# CON_REVC.net
KiCad netlist of a schematic drawn in EAGLE
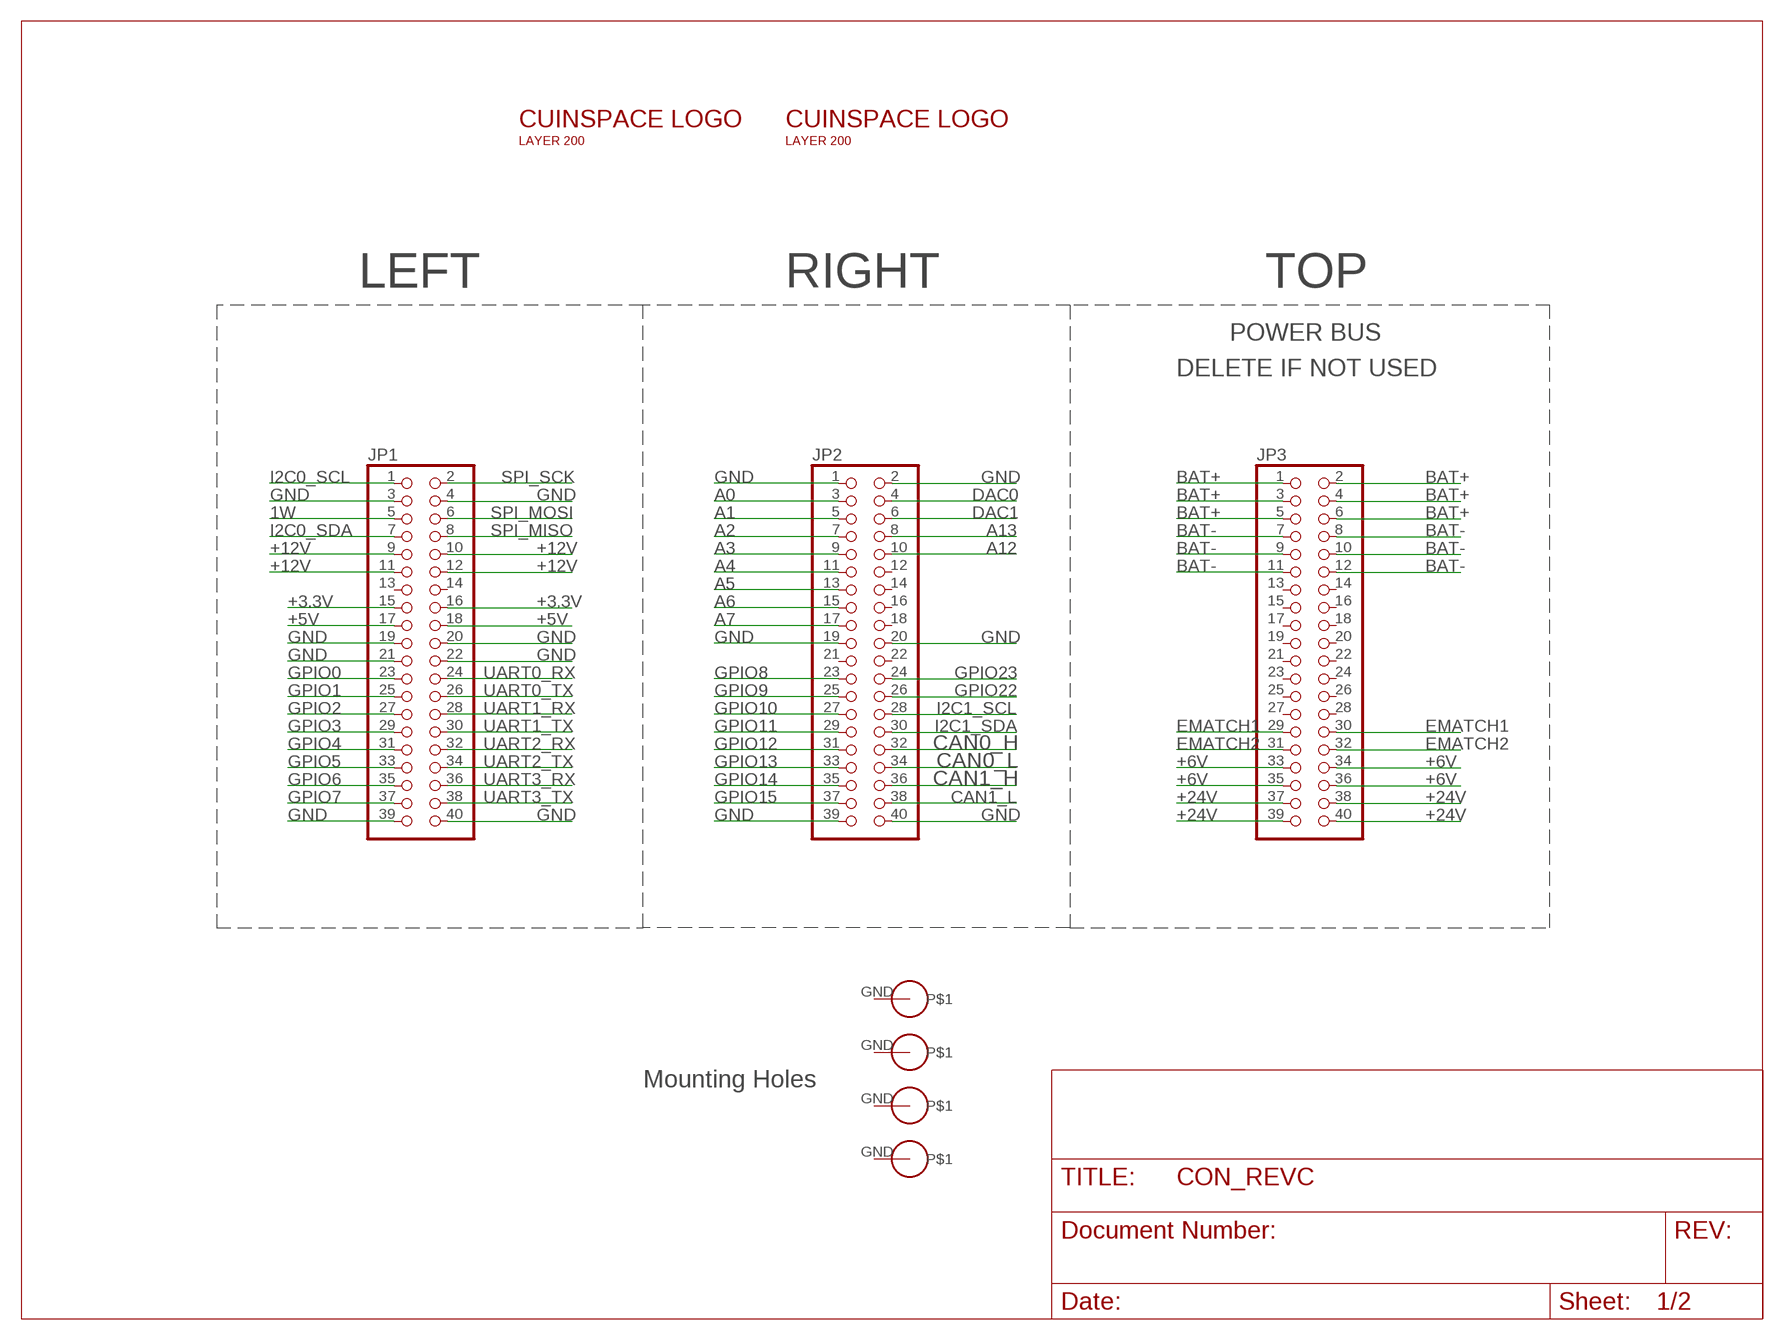
[diagram p0: schematic, sheet 1]
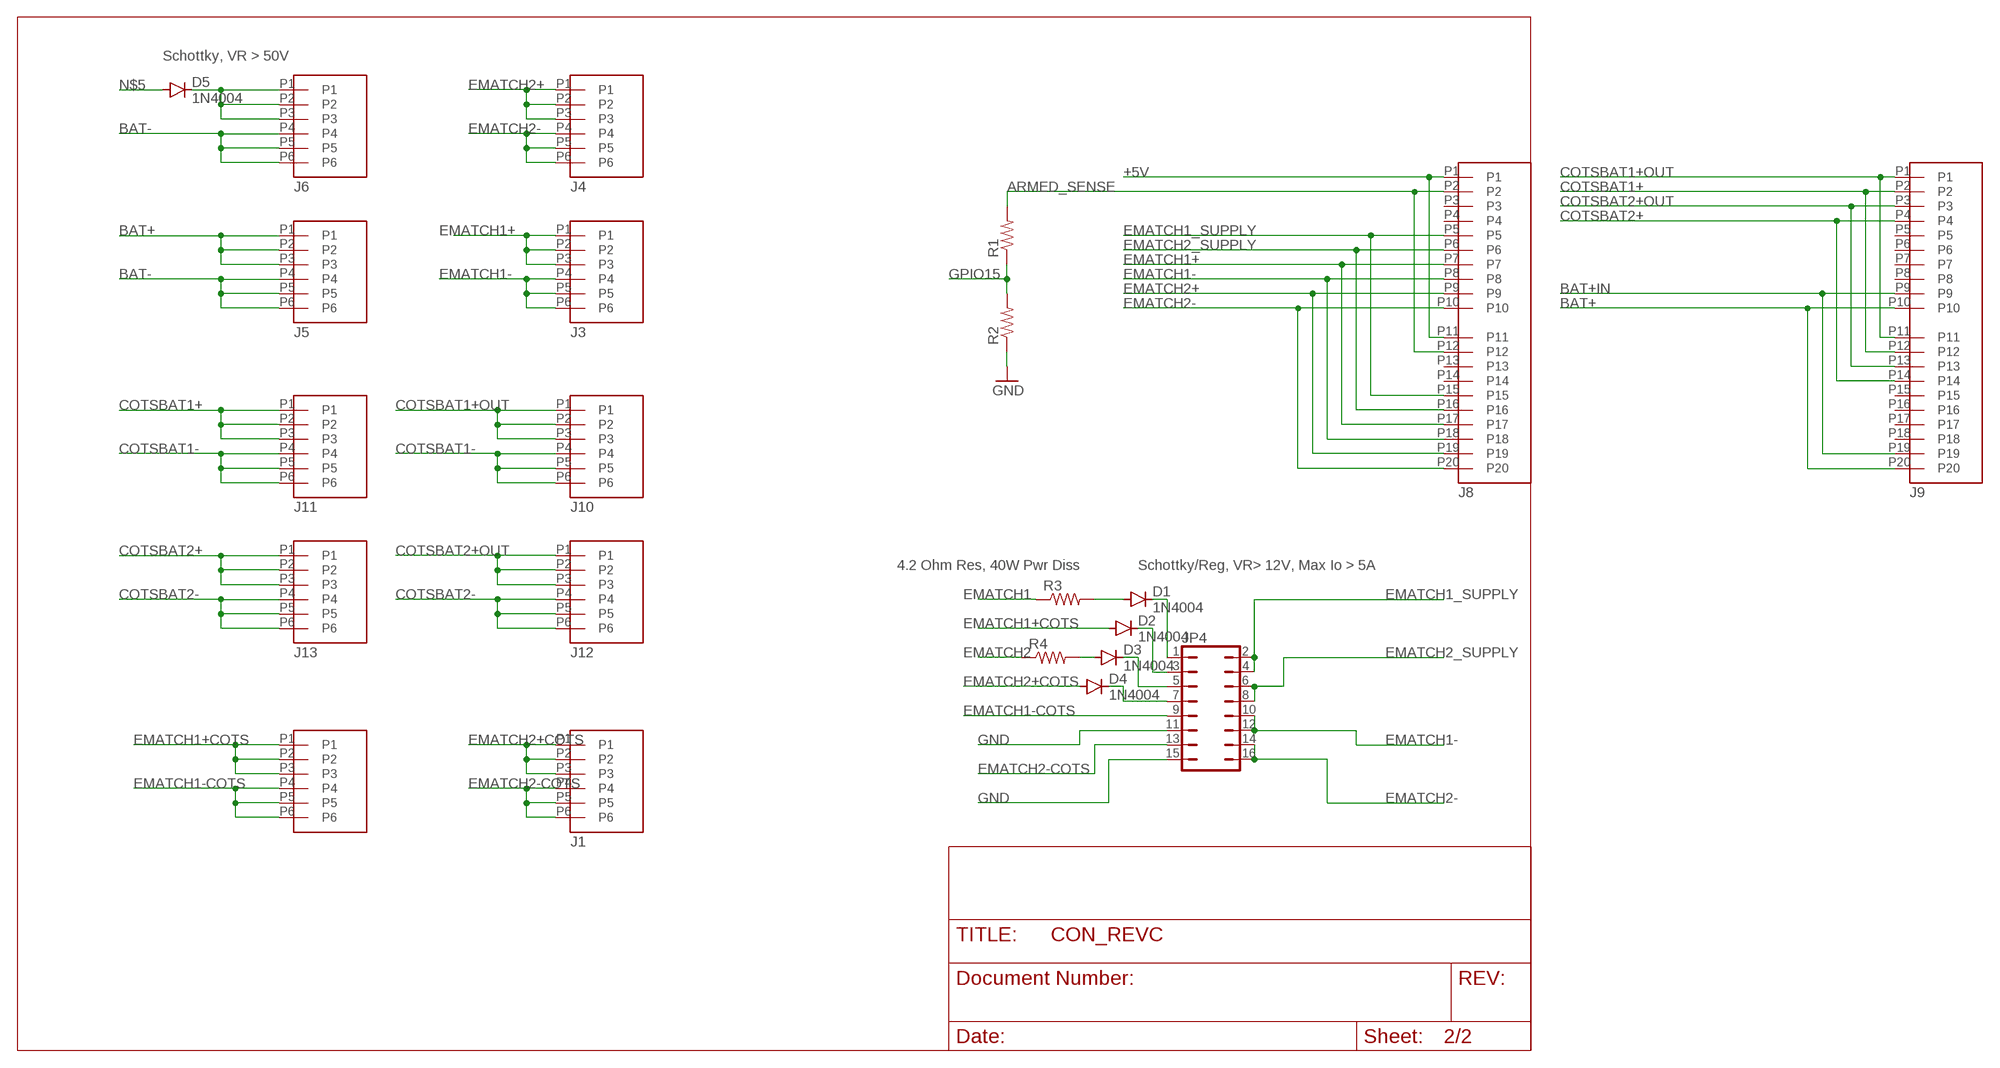
[diagram p1: schematic, sheet 2]

(export (version "E")
  (design (tool "Eeschema 10.0.6"))
  (components
    (comp (ref "D1")
      (value "1N4004")
      (footprint "eagle-import:DO41-10")
      (libsource (lib "eagle-import") (part "1N4004"))
    )
    (comp (ref "D2")
      (value "1N4004")
      (footprint "eagle-import:DO41-10")
      (libsource (lib "eagle-import") (part "1N4004"))
    )
    (comp (ref "D3")
      (value "1N4004")
      (footprint "eagle-import:DO41-10")
      (libsource (lib "eagle-import") (part "1N4004"))
    )
    (comp (ref "D4")
      (value "1N4004")
      (footprint "eagle-import:DO41-10")
      (libsource (lib "eagle-import") (part "1N4004"))
    )
    (comp (ref "D5")
      (value "1N4004")
      (footprint "eagle-import:DO41-10")
      (libsource (lib "eagle-import") (part "1N4004"))
    )
    (comp (ref "J1")
      (value "M80-5100642")
      (footprint "eagle-import:M80-5100642")
      (libsource (lib "eagle-import") (part "M80-5100642"))
    )
    (comp (ref "J2")
      (value "M80-5100642")
      (footprint "eagle-import:M80-5100642")
      (libsource (lib "eagle-import") (part "M80-5100642"))
    )
    (comp (ref "J3")
      (value "M80-5100642")
      (footprint "eagle-import:M80-5100642")
      (libsource (lib "eagle-import") (part "M80-5100642"))
    )
    (comp (ref "J4")
      (value "M80-5100642")
      (footprint "eagle-import:M80-5100642")
      (libsource (lib "eagle-import") (part "M80-5100642"))
    )
    (comp (ref "J5")
      (value "M80-5100642")
      (footprint "eagle-import:M80-5100642")
      (libsource (lib "eagle-import") (part "M80-5100642"))
    )
    (comp (ref "J6")
      (value "M80-5100642")
      (footprint "eagle-import:M80-5100642")
      (libsource (lib "eagle-import") (part "M80-5100642"))
    )
    (comp (ref "J8")
      (value "M80-5102042")
      (footprint "eagle-import:M80-5102042")
      (libsource (lib "eagle-import") (part "M80-5102042"))
    )
    (comp (ref "J9")
      (value "M80-5102042")
      (footprint "eagle-import:M80-5102042")
      (libsource (lib "eagle-import") (part "M80-5102042"))
    )
    (comp (ref "J10")
      (value "M80-5100642")
      (footprint "eagle-import:M80-5100642")
      (libsource (lib "eagle-import") (part "M80-5100642"))
    )
    (comp (ref "J11")
      (value "M80-5100642")
      (footprint "eagle-import:M80-5100642")
      (libsource (lib "eagle-import") (part "M80-5100642"))
    )
    (comp (ref "J12")
      (value "M80-5100642")
      (footprint "eagle-import:M80-5100642")
      (libsource (lib "eagle-import") (part "M80-5100642"))
    )
    (comp (ref "J13")
      (value "M80-5100642")
      (footprint "eagle-import:M80-5100642")
      (libsource (lib "eagle-import") (part "M80-5100642"))
    )
    (comp (ref "JP4")
      (value "JP8Q")
      (footprint "eagle-import:JP8Q")
      (libsource (lib "eagle-import") (part "JP8Q"))
    )
    (comp (ref "R1")
      (value "R-US_R0805")
      (footprint "eagle-import:R0805")
      (libsource (lib "eagle-import") (part "R-US_R0805"))
    )
    (comp (ref "R2")
      (value "R-US_R0805")
      (footprint "eagle-import:R0805")
      (libsource (lib "eagle-import") (part "R-US_R0805"))
    )
    (comp (ref "R3")
      (value "R-US_R0805")
      (footprint "eagle-import:R0805")
      (libsource (lib "eagle-import") (part "R-US_R0805"))
    )
    (comp (ref "R4")
      (value "R-US_R0805")
      (footprint "eagle-import:R0805")
      (libsource (lib "eagle-import") (part "R-US_R0805"))
    )
    (comp (ref "$$U$1")
      (value "PS/104-MOUNTING-HOLE")
      (footprint "eagle-import:PC_104-MOUNTING-HOLE")
      (libsource (lib "eagle-import") (part "PS/104-MOUNTING-HOLE"))
    )
    (comp (ref "JP1")
      (value "PINHD-2X20")
      (footprint "eagle-import:2X20")
      (libsource (lib "eagle-import") (part "PINHD-2X20"))
    )
    (comp (ref "JP2")
      (value "PINHD-2X20")
      (footprint "eagle-import:2X20")
      (libsource (lib "eagle-import") (part "PINHD-2X20"))
    )
    (comp (ref "JP3")
      (value "PINHD-2X20")
      (footprint "eagle-import:2X20")
      (libsource (lib "eagle-import") (part "PINHD-2X20"))
    )
    (comp (ref "U$1")
      (value "PS/104-MOUNTING-HOLE")
      (footprint "eagle-import:PC_104-MOUNTING-HOLE")
      (libsource (lib "eagle-import") (part "PS/104-MOUNTING-HOLE"))
    )
    (comp (ref "U$2")
      (value "PS/104-MOUNTING-HOLE")
      (footprint "eagle-import:PC_104-MOUNTING-HOLE")
      (libsource (lib "eagle-import") (part "PS/104-MOUNTING-HOLE"))
    )
    (comp (ref "U$3")
      (value "PS/104-MOUNTING-HOLE")
      (footprint "eagle-import:PC_104-MOUNTING-HOLE")
      (libsource (lib "eagle-import") (part "PS/104-MOUNTING-HOLE"))
    )
    (comp (ref "U$5")
      (value "INSPACE3CM_L")
      (footprint "eagle-import:INSPACE_3CM_LETTERS")
      (libsource (lib "eagle-import") (part "INSPACE3CM_L"))
    )
    (comp (ref "U$6")
      (value "INSPACE3CM_L")
      (footprint "eagle-import:INSPACE_3CM_LETTERS")
      (libsource (lib "eagle-import") (part "INSPACE3CM_L"))
    )
  )
  (nets
    (net (code "1") (name "+3.3V") (class "Default")
      (node (ref "JP1") (pin "15") (pinfunction "15_15") (pintype "passive"))
      (node (ref "JP1") (pin "16") (pinfunction "16_16") (pintype "passive"))
    )
    (net (code "2") (name "+5V") (class "Default")
      (node (ref "J8") (pin "P1") (pinfunction "P1_P1") (pintype "bidirectional"))
      (node (ref "J8") (pin "P11") (pinfunction "P11_P11") (pintype "bidirectional"))
      (node (ref "JP1") (pin "17") (pinfunction "17_17") (pintype "passive"))
      (node (ref "JP1") (pin "18") (pinfunction "18_18") (pintype "passive"))
    )
    (net (code "3") (name "+6V") (class "Default")
      (node (ref "JP3") (pin "33") (pinfunction "33_33") (pintype "passive"))
      (node (ref "JP3") (pin "34") (pinfunction "34_34") (pintype "passive"))
      (node (ref "JP3") (pin "35") (pinfunction "35_35") (pintype "passive"))
      (node (ref "JP3") (pin "36") (pinfunction "36_36") (pintype "passive"))
    )
    (net (code "4") (name "+12V") (class "Default")
      (node (ref "JP1") (pin "10") (pinfunction "10_10") (pintype "passive"))
      (node (ref "JP1") (pin "11") (pinfunction "11_11") (pintype "passive"))
      (node (ref "JP1") (pin "12") (pinfunction "12_12") (pintype "passive"))
      (node (ref "JP1") (pin "9") (pinfunction "9_9") (pintype "passive"))
    )
    (net (code "5") (name "+24V") (class "Default")
      (node (ref "JP3") (pin "37") (pinfunction "37_37") (pintype "passive"))
      (node (ref "JP3") (pin "38") (pinfunction "38_38") (pintype "passive"))
      (node (ref "JP3") (pin "39") (pinfunction "39_39") (pintype "passive"))
      (node (ref "JP3") (pin "40") (pinfunction "40_40") (pintype "passive"))
    )
    (net (code "6") (name "1W") (class "Default")
      (node (ref "JP1") (pin "5") (pinfunction "5_5") (pintype "passive"))
    )
    (net (code "7") (name "A0") (class "Default")
      (node (ref "JP2") (pin "3") (pinfunction "3_3") (pintype "passive"))
    )
    (net (code "8") (name "A1") (class "Default")
      (node (ref "JP2") (pin "5") (pinfunction "5_5") (pintype "passive"))
    )
    (net (code "9") (name "A2") (class "Default")
      (node (ref "JP2") (pin "7") (pinfunction "7_7") (pintype "passive"))
    )
    (net (code "10") (name "A3") (class "Default")
      (node (ref "JP2") (pin "9") (pinfunction "9_9") (pintype "passive"))
    )
    (net (code "11") (name "A4") (class "Default")
      (node (ref "JP2") (pin "11") (pinfunction "11_11") (pintype "passive"))
    )
    (net (code "12") (name "A5") (class "Default")
      (node (ref "JP2") (pin "13") (pinfunction "13_13") (pintype "passive"))
    )
    (net (code "13") (name "A6") (class "Default")
      (node (ref "JP2") (pin "15") (pinfunction "15_15") (pintype "passive"))
    )
    (net (code "14") (name "A7") (class "Default")
      (node (ref "JP2") (pin "17") (pinfunction "17_17") (pintype "passive"))
    )
    (net (code "15") (name "A12") (class "Default")
      (node (ref "JP2") (pin "10") (pinfunction "10_10") (pintype "passive"))
    )
    (net (code "16") (name "A13") (class "Default")
      (node (ref "JP2") (pin "8") (pinfunction "8_8") (pintype "passive"))
    )
    (net (code "17") (name "ARMED_SENSE") (class "Default")
      (node (ref "J8") (pin "P12") (pinfunction "P12_P12") (pintype "bidirectional"))
      (node (ref "J8") (pin "P2") (pinfunction "P2_P2") (pintype "bidirectional"))
      (node (ref "R1") (pin "2") (pinfunction "2_2") (pintype "passive"))
    )
    (net (code "18") (name "BAT+") (class "Default")
      (node (ref "J5") (pin "P1") (pinfunction "P1_P1") (pintype "bidirectional"))
      (node (ref "J5") (pin "P2") (pinfunction "P2_P2") (pintype "bidirectional"))
      (node (ref "J5") (pin "P3") (pinfunction "P3_P3") (pintype "bidirectional"))
      (node (ref "J9") (pin "P10") (pinfunction "P10_P10") (pintype "bidirectional"))
      (node (ref "J9") (pin "P20") (pinfunction "P20_P20") (pintype "bidirectional"))
      (node (ref "JP3") (pin "1") (pinfunction "1_1") (pintype "passive"))
      (node (ref "JP3") (pin "2") (pinfunction "2_2") (pintype "passive"))
      (node (ref "JP3") (pin "3") (pinfunction "3_3") (pintype "passive"))
      (node (ref "JP3") (pin "4") (pinfunction "4_4") (pintype "passive"))
      (node (ref "JP3") (pin "5") (pinfunction "5_5") (pintype "passive"))
      (node (ref "JP3") (pin "6") (pinfunction "6_6") (pintype "passive"))
    )
    (net (code "19") (name "BAT+IN") (class "Default")
      (node (ref "D5") (pin "C") (pinfunction "C_C") (pintype "passive"))
      (node (ref "J6") (pin "P1") (pinfunction "P1_P1") (pintype "bidirectional"))
      (node (ref "J6") (pin "P2") (pinfunction "P2_P2") (pintype "bidirectional"))
      (node (ref "J6") (pin "P3") (pinfunction "P3_P3") (pintype "bidirectional"))
      (node (ref "J9") (pin "P19") (pinfunction "P19_P19") (pintype "bidirectional"))
      (node (ref "J9") (pin "P9") (pinfunction "P9_P9") (pintype "bidirectional"))
    )
    (net (code "20") (name "BAT-") (class "Default")
      (node (ref "J5") (pin "P4") (pinfunction "P4_P4") (pintype "bidirectional"))
      (node (ref "J5") (pin "P5") (pinfunction "P5_P5") (pintype "bidirectional"))
      (node (ref "J5") (pin "P6") (pinfunction "P6_P6") (pintype "bidirectional"))
      (node (ref "J6") (pin "P4") (pinfunction "P4_P4") (pintype "bidirectional"))
      (node (ref "J6") (pin "P5") (pinfunction "P5_P5") (pintype "bidirectional"))
      (node (ref "J6") (pin "P6") (pinfunction "P6_P6") (pintype "bidirectional"))
      (node (ref "JP3") (pin "10") (pinfunction "10_10") (pintype "passive"))
      (node (ref "JP3") (pin "11") (pinfunction "11_11") (pintype "passive"))
      (node (ref "JP3") (pin "12") (pinfunction "12_12") (pintype "passive"))
      (node (ref "JP3") (pin "7") (pinfunction "7_7") (pintype "passive"))
      (node (ref "JP3") (pin "8") (pinfunction "8_8") (pintype "passive"))
      (node (ref "JP3") (pin "9") (pinfunction "9_9") (pintype "passive"))
    )
    (net (code "21") (name "CAN0_H") (class "Default")
      (node (ref "JP2") (pin "32") (pinfunction "32_32") (pintype "passive"))
    )
    (net (code "22") (name "CAN0_L") (class "Default")
      (node (ref "JP2") (pin "34") (pinfunction "34_34") (pintype "passive"))
    )
    (net (code "23") (name "CAN1_H") (class "Default")
      (node (ref "JP2") (pin "36") (pinfunction "36_36") (pintype "passive"))
    )
    (net (code "24") (name "CAN1_L") (class "Default")
      (node (ref "JP2") (pin "38") (pinfunction "38_38") (pintype "passive"))
    )
    (net (code "25") (name "COTSBAT1+") (class "Default")
      (node (ref "J11") (pin "P1") (pinfunction "P1_P1") (pintype "bidirectional"))
      (node (ref "J11") (pin "P2") (pinfunction "P2_P2") (pintype "bidirectional"))
      (node (ref "J11") (pin "P3") (pinfunction "P3_P3") (pintype "bidirectional"))
      (node (ref "J9") (pin "P12") (pinfunction "P12_P12") (pintype "bidirectional"))
      (node (ref "J9") (pin "P2") (pinfunction "P2_P2") (pintype "bidirectional"))
    )
    (net (code "26") (name "COTSBAT1+OUT") (class "Default")
      (node (ref "J10") (pin "P1") (pinfunction "P1_P1") (pintype "bidirectional"))
      (node (ref "J10") (pin "P2") (pinfunction "P2_P2") (pintype "bidirectional"))
      (node (ref "J10") (pin "P3") (pinfunction "P3_P3") (pintype "bidirectional"))
      (node (ref "J9") (pin "P1") (pinfunction "P1_P1") (pintype "bidirectional"))
      (node (ref "J9") (pin "P11") (pinfunction "P11_P11") (pintype "bidirectional"))
    )
    (net (code "27") (name "COTSBAT1-") (class "Default")
      (node (ref "J10") (pin "P4") (pinfunction "P4_P4") (pintype "bidirectional"))
      (node (ref "J10") (pin "P5") (pinfunction "P5_P5") (pintype "bidirectional"))
      (node (ref "J10") (pin "P6") (pinfunction "P6_P6") (pintype "bidirectional"))
      (node (ref "J11") (pin "P4") (pinfunction "P4_P4") (pintype "bidirectional"))
      (node (ref "J11") (pin "P5") (pinfunction "P5_P5") (pintype "bidirectional"))
      (node (ref "J11") (pin "P6") (pinfunction "P6_P6") (pintype "bidirectional"))
    )
    (net (code "28") (name "COTSBAT2+") (class "Default")
      (node (ref "J13") (pin "P1") (pinfunction "P1_P1") (pintype "bidirectional"))
      (node (ref "J13") (pin "P2") (pinfunction "P2_P2") (pintype "bidirectional"))
      (node (ref "J13") (pin "P3") (pinfunction "P3_P3") (pintype "bidirectional"))
      (node (ref "J9") (pin "P14") (pinfunction "P14_P14") (pintype "bidirectional"))
      (node (ref "J9") (pin "P4") (pinfunction "P4_P4") (pintype "bidirectional"))
    )
    (net (code "29") (name "COTSBAT2+OUT") (class "Default")
      (node (ref "J12") (pin "P1") (pinfunction "P1_P1") (pintype "bidirectional"))
      (node (ref "J12") (pin "P2") (pinfunction "P2_P2") (pintype "bidirectional"))
      (node (ref "J12") (pin "P3") (pinfunction "P3_P3") (pintype "bidirectional"))
      (node (ref "J9") (pin "P13") (pinfunction "P13_P13") (pintype "bidirectional"))
      (node (ref "J9") (pin "P3") (pinfunction "P3_P3") (pintype "bidirectional"))
    )
    (net (code "30") (name "COTSBAT2-") (class "Default")
      (node (ref "J12") (pin "P4") (pinfunction "P4_P4") (pintype "bidirectional"))
      (node (ref "J12") (pin "P5") (pinfunction "P5_P5") (pintype "bidirectional"))
      (node (ref "J12") (pin "P6") (pinfunction "P6_P6") (pintype "bidirectional"))
      (node (ref "J13") (pin "P4") (pinfunction "P4_P4") (pintype "bidirectional"))
      (node (ref "J13") (pin "P5") (pinfunction "P5_P5") (pintype "bidirectional"))
      (node (ref "J13") (pin "P6") (pinfunction "P6_P6") (pintype "bidirectional"))
    )
    (net (code "31") (name "DAC0") (class "Default")
      (node (ref "JP2") (pin "4") (pinfunction "4_4") (pintype "passive"))
    )
    (net (code "32") (name "DAC1") (class "Default")
      (node (ref "JP2") (pin "6") (pinfunction "6_6") (pintype "passive"))
    )
    (net (code "33") (name "EMATCH1") (class "Default")
      (node (ref "JP3") (pin "29") (pinfunction "29_29") (pintype "passive"))
      (node (ref "JP3") (pin "30") (pinfunction "30_30") (pintype "passive"))
      (node (ref "R3") (pin "1") (pinfunction "1_1") (pintype "passive"))
    )
    (net (code "34") (name "EMATCH1+") (class "Default")
      (node (ref "J3") (pin "P1") (pinfunction "P1_P1") (pintype "bidirectional"))
      (node (ref "J3") (pin "P2") (pinfunction "P2_P2") (pintype "bidirectional"))
      (node (ref "J3") (pin "P3") (pinfunction "P3_P3") (pintype "bidirectional"))
      (node (ref "J8") (pin "P17") (pinfunction "P17_P17") (pintype "bidirectional"))
      (node (ref "J8") (pin "P7") (pinfunction "P7_P7") (pintype "bidirectional"))
    )
    (net (code "35") (name "EMATCH1+COTS") (class "Default")
      (node (ref "D2") (pin "A") (pinfunction "A_A") (pintype "passive"))
      (node (ref "J2") (pin "P1") (pinfunction "P1_P1") (pintype "bidirectional"))
      (node (ref "J2") (pin "P2") (pinfunction "P2_P2") (pintype "bidirectional"))
      (node (ref "J2") (pin "P3") (pinfunction "P3_P3") (pintype "bidirectional"))
    )
    (net (code "36") (name "EMATCH1-") (class "Default")
      (node (ref "J3") (pin "P4") (pinfunction "P4_P4") (pintype "bidirectional"))
      (node (ref "J3") (pin "P5") (pinfunction "P5_P5") (pintype "bidirectional"))
      (node (ref "J3") (pin "P6") (pinfunction "P6_P6") (pintype "bidirectional"))
      (node (ref "J8") (pin "P18") (pinfunction "P18_P18") (pintype "bidirectional"))
      (node (ref "J8") (pin "P8") (pinfunction "P8_P8") (pintype "bidirectional"))
      (node (ref "JP4") (pin "10") (pinfunction "10_10") (pintype "passive"))
      (node (ref "JP4") (pin "12") (pinfunction "12_12") (pintype "passive"))
    )
    (net (code "37") (name "EMATCH1-COTS") (class "Default")
      (node (ref "J2") (pin "P4") (pinfunction "P4_P4") (pintype "bidirectional"))
      (node (ref "J2") (pin "P5") (pinfunction "P5_P5") (pintype "bidirectional"))
      (node (ref "J2") (pin "P6") (pinfunction "P6_P6") (pintype "bidirectional"))
      (node (ref "JP4") (pin "9") (pinfunction "9_9") (pintype "passive"))
    )
    (net (code "38") (name "EMATCH1_SUPPLY") (class "Default")
      (node (ref "J8") (pin "P15") (pinfunction "P15_P15") (pintype "bidirectional"))
      (node (ref "J8") (pin "P5") (pinfunction "P5_P5") (pintype "bidirectional"))
      (node (ref "JP4") (pin "2") (pinfunction "2_2") (pintype "passive"))
      (node (ref "JP4") (pin "4") (pinfunction "4_4") (pintype "passive"))
    )
    (net (code "39") (name "EMATCH2") (class "Default")
      (node (ref "JP3") (pin "31") (pinfunction "31_31") (pintype "passive"))
      (node (ref "JP3") (pin "32") (pinfunction "32_32") (pintype "passive"))
      (node (ref "R4") (pin "1") (pinfunction "1_1") (pintype "passive"))
    )
    (net (code "40") (name "EMATCH2+") (class "Default")
      (node (ref "J4") (pin "P1") (pinfunction "P1_P1") (pintype "bidirectional"))
      (node (ref "J4") (pin "P2") (pinfunction "P2_P2") (pintype "bidirectional"))
      (node (ref "J4") (pin "P3") (pinfunction "P3_P3") (pintype "bidirectional"))
      (node (ref "J8") (pin "P19") (pinfunction "P19_P19") (pintype "bidirectional"))
      (node (ref "J8") (pin "P9") (pinfunction "P9_P9") (pintype "bidirectional"))
    )
    (net (code "41") (name "EMATCH2+COTS") (class "Default")
      (node (ref "D4") (pin "A") (pinfunction "A_A") (pintype "passive"))
      (node (ref "J1") (pin "P1") (pinfunction "P1_P1") (pintype "bidirectional"))
      (node (ref "J1") (pin "P2") (pinfunction "P2_P2") (pintype "bidirectional"))
      (node (ref "J1") (pin "P3") (pinfunction "P3_P3") (pintype "bidirectional"))
    )
    (net (code "42") (name "EMATCH2-") (class "Default")
      (node (ref "J4") (pin "P4") (pinfunction "P4_P4") (pintype "bidirectional"))
      (node (ref "J4") (pin "P5") (pinfunction "P5_P5") (pintype "bidirectional"))
      (node (ref "J4") (pin "P6") (pinfunction "P6_P6") (pintype "bidirectional"))
      (node (ref "J8") (pin "P10") (pinfunction "P10_P10") (pintype "bidirectional"))
      (node (ref "J8") (pin "P20") (pinfunction "P20_P20") (pintype "bidirectional"))
      (node (ref "JP4") (pin "14") (pinfunction "14_14") (pintype "passive"))
      (node (ref "JP4") (pin "16") (pinfunction "16_16") (pintype "passive"))
    )
    (net (code "43") (name "EMATCH2-COTS") (class "Default")
      (node (ref "J1") (pin "P4") (pinfunction "P4_P4") (pintype "bidirectional"))
      (node (ref "J1") (pin "P5") (pinfunction "P5_P5") (pintype "bidirectional"))
      (node (ref "J1") (pin "P6") (pinfunction "P6_P6") (pintype "bidirectional"))
      (node (ref "JP4") (pin "13") (pinfunction "13_13") (pintype "passive"))
    )
    (net (code "44") (name "EMATCH2_SUPPLY") (class "Default")
      (node (ref "J8") (pin "P16") (pinfunction "P16_P16") (pintype "bidirectional"))
      (node (ref "J8") (pin "P6") (pinfunction "P6_P6") (pintype "bidirectional"))
      (node (ref "JP4") (pin "6") (pinfunction "6_6") (pintype "passive"))
      (node (ref "JP4") (pin "8") (pinfunction "8_8") (pintype "passive"))
    )
    (net (code "45") (name "GND") (class "Default")
      (node (ref "JP1") (pin "19") (pinfunction "19_19") (pintype "passive"))
      (node (ref "JP1") (pin "20") (pinfunction "20_20") (pintype "passive"))
      (node (ref "JP1") (pin "21") (pinfunction "21_21") (pintype "passive"))
      (node (ref "JP1") (pin "22") (pinfunction "22_22") (pintype "passive"))
      (node (ref "JP1") (pin "3") (pinfunction "3_3") (pintype "passive"))
      (node (ref "JP1") (pin "39") (pinfunction "39_39") (pintype "passive"))
      (node (ref "JP1") (pin "4") (pinfunction "4_4") (pintype "passive"))
      (node (ref "JP1") (pin "40") (pinfunction "40_40") (pintype "passive"))
      (node (ref "JP2") (pin "1") (pinfunction "1_1") (pintype "passive"))
      (node (ref "JP2") (pin "19") (pinfunction "19_19") (pintype "passive"))
      (node (ref "JP2") (pin "2") (pinfunction "2_2") (pintype "passive"))
      (node (ref "JP2") (pin "20") (pinfunction "20_20") (pintype "passive"))
      (node (ref "JP2") (pin "39") (pinfunction "39_39") (pintype "passive"))
      (node (ref "JP2") (pin "40") (pinfunction "40_40") (pintype "passive"))
      (node (ref "JP4") (pin "11") (pinfunction "11_11") (pintype "passive"))
      (node (ref "JP4") (pin "15") (pinfunction "15_15") (pintype "passive"))
      (node (ref "R2") (pin "1") (pinfunction "1_1") (pintype "passive"))
    )
    (net (code "46") (name "GPIO0") (class "Default")
      (node (ref "JP1") (pin "23") (pinfunction "23_23") (pintype "passive"))
    )
    (net (code "47") (name "GPIO1") (class "Default")
      (node (ref "JP1") (pin "25") (pinfunction "25_25") (pintype "passive"))
    )
    (net (code "48") (name "GPIO2") (class "Default")
      (node (ref "JP1") (pin "27") (pinfunction "27_27") (pintype "passive"))
    )
    (net (code "49") (name "GPIO3") (class "Default")
      (node (ref "JP1") (pin "29") (pinfunction "29_29") (pintype "passive"))
    )
    (net (code "50") (name "GPIO4") (class "Default")
      (node (ref "JP1") (pin "31") (pinfunction "31_31") (pintype "passive"))
    )
    (net (code "51") (name "GPIO5") (class "Default")
      (node (ref "JP1") (pin "33") (pinfunction "33_33") (pintype "passive"))
    )
    (net (code "52") (name "GPIO6") (class "Default")
      (node (ref "JP1") (pin "35") (pinfunction "35_35") (pintype "passive"))
    )
    (net (code "53") (name "GPIO7") (class "Default")
      (node (ref "JP1") (pin "37") (pinfunction "37_37") (pintype "passive"))
    )
    (net (code "54") (name "GPIO8") (class "Default")
      (node (ref "JP2") (pin "23") (pinfunction "23_23") (pintype "passive"))
    )
    (net (code "55") (name "GPIO9") (class "Default")
      (node (ref "JP2") (pin "25") (pinfunction "25_25") (pintype "passive"))
    )
    (net (code "56") (name "GPIO10") (class "Default")
      (node (ref "JP2") (pin "27") (pinfunction "27_27") (pintype "passive"))
    )
    (net (code "57") (name "GPIO11") (class "Default")
      (node (ref "JP2") (pin "29") (pinfunction "29_29") (pintype "passive"))
    )
    (net (code "58") (name "GPIO12") (class "Default")
      (node (ref "JP2") (pin "31") (pinfunction "31_31") (pintype "passive"))
    )
    (net (code "59") (name "GPIO13") (class "Default")
      (node (ref "JP2") (pin "33") (pinfunction "33_33") (pintype "passive"))
    )
    (net (code "60") (name "GPIO14") (class "Default")
      (node (ref "JP2") (pin "35") (pinfunction "35_35") (pintype "passive"))
    )
    (net (code "61") (name "GPIO15") (class "Default")
      (node (ref "JP2") (pin "37") (pinfunction "37_37") (pintype "passive"))
      (node (ref "R1") (pin "1") (pinfunction "1_1") (pintype "passive"))
      (node (ref "R2") (pin "2") (pinfunction "2_2") (pintype "passive"))
    )
    (net (code "62") (name "GPIO22") (class "Default")
      (node (ref "JP2") (pin "26") (pinfunction "26_26") (pintype "passive"))
    )
    (net (code "63") (name "GPIO23") (class "Default")
      (node (ref "JP2") (pin "24") (pinfunction "24_24") (pintype "passive"))
    )
    (net (code "64") (name "I2C0_SCL") (class "Default")
      (node (ref "JP1") (pin "1") (pinfunction "1_1") (pintype "passive"))
    )
    (net (code "65") (name "I2C0_SDA") (class "Default")
      (node (ref "JP1") (pin "7") (pinfunction "7_7") (pintype "passive"))
    )
    (net (code "66") (name "I2C1_SCL") (class "Default")
      (node (ref "JP2") (pin "28") (pinfunction "28_28") (pintype "passive"))
    )
    (net (code "67") (name "I2C1_SDA") (class "Default")
      (node (ref "JP2") (pin "30") (pinfunction "30_30") (pintype "passive"))
    )
    (net (code "68") (name "N$5") (class "Default")
      (node (ref "D5") (pin "A") (pinfunction "A_A") (pintype "passive"))
    )
    (net (code "69") (name "Net-(D1-PadA)") (class "Default")
      (node (ref "D1") (pin "A") (pinfunction "A_A") (pintype "passive"))
      (node (ref "R3") (pin "2") (pinfunction "2_2") (pintype "passive"))
    )
    (net (code "70") (name "Net-(D1-PadC)") (class "Default")
      (node (ref "D1") (pin "C") (pinfunction "C_C") (pintype "passive"))
      (node (ref "JP4") (pin "1") (pinfunction "1_1") (pintype "passive"))
    )
    (net (code "71") (name "Net-(D2-PadC)") (class "Default")
      (node (ref "D2") (pin "C") (pinfunction "C_C") (pintype "passive"))
      (node (ref "JP4") (pin "3") (pinfunction "3_3") (pintype "passive"))
    )
    (net (code "72") (name "Net-(D3-PadA)") (class "Default")
      (node (ref "D3") (pin "A") (pinfunction "A_A") (pintype "passive"))
      (node (ref "R4") (pin "2") (pinfunction "2_2") (pintype "passive"))
    )
    (net (code "73") (name "Net-(D3-PadC)") (class "Default")
      (node (ref "D3") (pin "C") (pinfunction "C_C") (pintype "passive"))
      (node (ref "JP4") (pin "5") (pinfunction "5_5") (pintype "passive"))
    )
    (net (code "74") (name "Net-(D4-PadC)") (class "Default")
      (node (ref "D4") (pin "C") (pinfunction "C_C") (pintype "passive"))
      (node (ref "JP4") (pin "7") (pinfunction "7_7") (pintype "passive"))
    )
    (net (code "75") (name "SPI_MISO") (class "Default")
      (node (ref "JP1") (pin "8") (pinfunction "8_8") (pintype "passive"))
    )
    (net (code "76") (name "SPI_MOSI") (class "Default")
      (node (ref "JP1") (pin "6") (pinfunction "6_6") (pintype "passive"))
    )
    (net (code "77") (name "SPI_SCK") (class "Default")
      (node (ref "JP1") (pin "2") (pinfunction "2_2") (pintype "passive"))
    )
    (net (code "78") (name "UART0_RX") (class "Default")
      (node (ref "JP1") (pin "24") (pinfunction "24_24") (pintype "passive"))
    )
    (net (code "79") (name "UART0_TX") (class "Default")
      (node (ref "JP1") (pin "26") (pinfunction "26_26") (pintype "passive"))
    )
    (net (code "80") (name "UART1_RX") (class "Default")
      (node (ref "JP1") (pin "28") (pinfunction "28_28") (pintype "passive"))
    )
    (net (code "81") (name "UART1_TX") (class "Default")
      (node (ref "JP1") (pin "30") (pinfunction "30_30") (pintype "passive"))
    )
    (net (code "82") (name "UART2_RX") (class "Default")
      (node (ref "JP1") (pin "32") (pinfunction "32_32") (pintype "passive"))
    )
    (net (code "83") (name "UART2_TX") (class "Default")
      (node (ref "JP1") (pin "34") (pinfunction "34_34") (pintype "passive"))
    )
    (net (code "84") (name "UART3_RX") (class "Default")
      (node (ref "JP1") (pin "36") (pinfunction "36_36") (pintype "passive"))
    )
    (net (code "85") (name "UART3_TX") (class "Default")
      (node (ref "JP1") (pin "38") (pinfunction "38_38") (pintype "passive"))
    )
    (net (code "86") (name "unconnected-($$U$1-P$1-PadGND)") (class "Default")
      (node (ref "$$U$1") (pin "GND") (pinfunction "P$1_GND") (pintype "bidirectional"))
    )
    (net (code "87") (name "unconnected-(J8-PadP3)") (class "Default")
      (node (ref "J8") (pin "P3") (pinfunction "P3_P3") (pintype "bidirectional"))
    )
    (net (code "88") (name "unconnected-(J8-PadP4)") (class "Default")
      (node (ref "J8") (pin "P4") (pinfunction "P4_P4") (pintype "bidirectional"))
    )
    (net (code "89") (name "unconnected-(J8-PadP13)") (class "Default")
      (node (ref "J8") (pin "P13") (pinfunction "P13_P13") (pintype "bidirectional"))
    )
    (net (code "90") (name "unconnected-(J8-PadP14)") (class "Default")
      (node (ref "J8") (pin "P14") (pinfunction "P14_P14") (pintype "bidirectional"))
    )
    (net (code "91") (name "unconnected-(J9-PadP5)") (class "Default")
      (node (ref "J9") (pin "P5") (pinfunction "P5_P5") (pintype "bidirectional"))
    )
    (net (code "92") (name "unconnected-(J9-PadP6)") (class "Default")
      (node (ref "J9") (pin "P6") (pinfunction "P6_P6") (pintype "bidirectional"))
    )
    (net (code "93") (name "unconnected-(J9-PadP7)") (class "Default")
      (node (ref "J9") (pin "P7") (pinfunction "P7_P7") (pintype "bidirectional"))
    )
    (net (code "94") (name "unconnected-(J9-PadP8)") (class "Default")
      (node (ref "J9") (pin "P8") (pinfunction "P8_P8") (pintype "bidirectional"))
    )
    (net (code "95") (name "unconnected-(J9-PadP15)") (class "Default")
      (node (ref "J9") (pin "P15") (pinfunction "P15_P15") (pintype "bidirectional"))
    )
    (net (code "96") (name "unconnected-(J9-PadP16)") (class "Default")
      (node (ref "J9") (pin "P16") (pinfunction "P16_P16") (pintype "bidirectional"))
    )
    (net (code "97") (name "unconnected-(J9-PadP17)") (class "Default")
      (node (ref "J9") (pin "P17") (pinfunction "P17_P17") (pintype "bidirectional"))
    )
    (net (code "98") (name "unconnected-(J9-PadP18)") (class "Default")
      (node (ref "J9") (pin "P18") (pinfunction "P18_P18") (pintype "bidirectional"))
    )
    (net (code "99") (name "unconnected-(JP1-Pad13)") (class "Default")
      (node (ref "JP1") (pin "13") (pinfunction "13_13") (pintype "passive"))
    )
    (net (code "100") (name "unconnected-(JP1-Pad14)") (class "Default")
      (node (ref "JP1") (pin "14") (pinfunction "14_14") (pintype "passive"))
    )
    (net (code "101") (name "unconnected-(JP2-Pad12)") (class "Default")
      (node (ref "JP2") (pin "12") (pinfunction "12_12") (pintype "passive"))
    )
    (net (code "102") (name "unconnected-(JP2-Pad14)") (class "Default")
      (node (ref "JP2") (pin "14") (pinfunction "14_14") (pintype "passive"))
    )
    (net (code "103") (name "unconnected-(JP2-Pad16)") (class "Default")
      (node (ref "JP2") (pin "16") (pinfunction "16_16") (pintype "passive"))
    )
    (net (code "104") (name "unconnected-(JP2-Pad18)") (class "Default")
      (node (ref "JP2") (pin "18") (pinfunction "18_18") (pintype "passive"))
    )
    (net (code "105") (name "unconnected-(JP2-Pad21)") (class "Default")
      (node (ref "JP2") (pin "21") (pinfunction "21_21") (pintype "passive"))
    )
    (net (code "106") (name "unconnected-(JP2-Pad22)") (class "Default")
      (node (ref "JP2") (pin "22") (pinfunction "22_22") (pintype "passive"))
    )
    (net (code "107") (name "unconnected-(JP3-Pad13)") (class "Default")
      (node (ref "JP3") (pin "13") (pinfunction "13_13") (pintype "passive"))
    )
    (net (code "108") (name "unconnected-(JP3-Pad14)") (class "Default")
      (node (ref "JP3") (pin "14") (pinfunction "14_14") (pintype "passive"))
    )
    (net (code "109") (name "unconnected-(JP3-Pad15)") (class "Default")
      (node (ref "JP3") (pin "15") (pinfunction "15_15") (pintype "passive"))
    )
    (net (code "110") (name "unconnected-(JP3-Pad16)") (class "Default")
      (node (ref "JP3") (pin "16") (pinfunction "16_16") (pintype "passive"))
    )
    (net (code "111") (name "unconnected-(JP3-Pad17)") (class "Default")
      (node (ref "JP3") (pin "17") (pinfunction "17_17") (pintype "passive"))
    )
    (net (code "112") (name "unconnected-(JP3-Pad18)") (class "Default")
      (node (ref "JP3") (pin "18") (pinfunction "18_18") (pintype "passive"))
    )
    (net (code "113") (name "unconnected-(JP3-Pad19)") (class "Default")
      (node (ref "JP3") (pin "19") (pinfunction "19_19") (pintype "passive"))
    )
    (net (code "114") (name "unconnected-(JP3-Pad20)") (class "Default")
      (node (ref "JP3") (pin "20") (pinfunction "20_20") (pintype "passive"))
    )
    (net (code "115") (name "unconnected-(JP3-Pad21)") (class "Default")
      (node (ref "JP3") (pin "21") (pinfunction "21_21") (pintype "passive"))
    )
    (net (code "116") (name "unconnected-(JP3-Pad22)") (class "Default")
      (node (ref "JP3") (pin "22") (pinfunction "22_22") (pintype "passive"))
    )
    (net (code "117") (name "unconnected-(JP3-Pad23)") (class "Default")
      (node (ref "JP3") (pin "23") (pinfunction "23_23") (pintype "passive"))
    )
    (net (code "118") (name "unconnected-(JP3-Pad24)") (class "Default")
      (node (ref "JP3") (pin "24") (pinfunction "24_24") (pintype "passive"))
    )
    (net (code "119") (name "unconnected-(JP3-Pad25)") (class "Default")
      (node (ref "JP3") (pin "25") (pinfunction "25_25") (pintype "passive"))
    )
    (net (code "120") (name "unconnected-(JP3-Pad26)") (class "Default")
      (node (ref "JP3") (pin "26") (pinfunction "26_26") (pintype "passive"))
    )
    (net (code "121") (name "unconnected-(JP3-Pad27)") (class "Default")
      (node (ref "JP3") (pin "27") (pinfunction "27_27") (pintype "passive"))
    )
    (net (code "122") (name "unconnected-(JP3-Pad28)") (class "Default")
      (node (ref "JP3") (pin "28") (pinfunction "28_28") (pintype "passive"))
    )
    (net (code "123") (name "unconnected-(U$1-P$1-PadGND)") (class "Default")
      (node (ref "U$1") (pin "GND") (pinfunction "P$1_GND") (pintype "bidirectional"))
    )
    (net (code "124") (name "unconnected-(U$2-P$1-PadGND)") (class "Default")
      (node (ref "U$2") (pin "GND") (pinfunction "P$1_GND") (pintype "bidirectional"))
    )
    (net (code "125") (name "unconnected-(U$3-P$1-PadGND)") (class "Default")
      (node (ref "U$3") (pin "GND") (pinfunction "P$1_GND") (pintype "bidirectional"))
    )
  )
)
